# main_16_writer.net
KiCad netlist of a schematic drawn in EAGLE
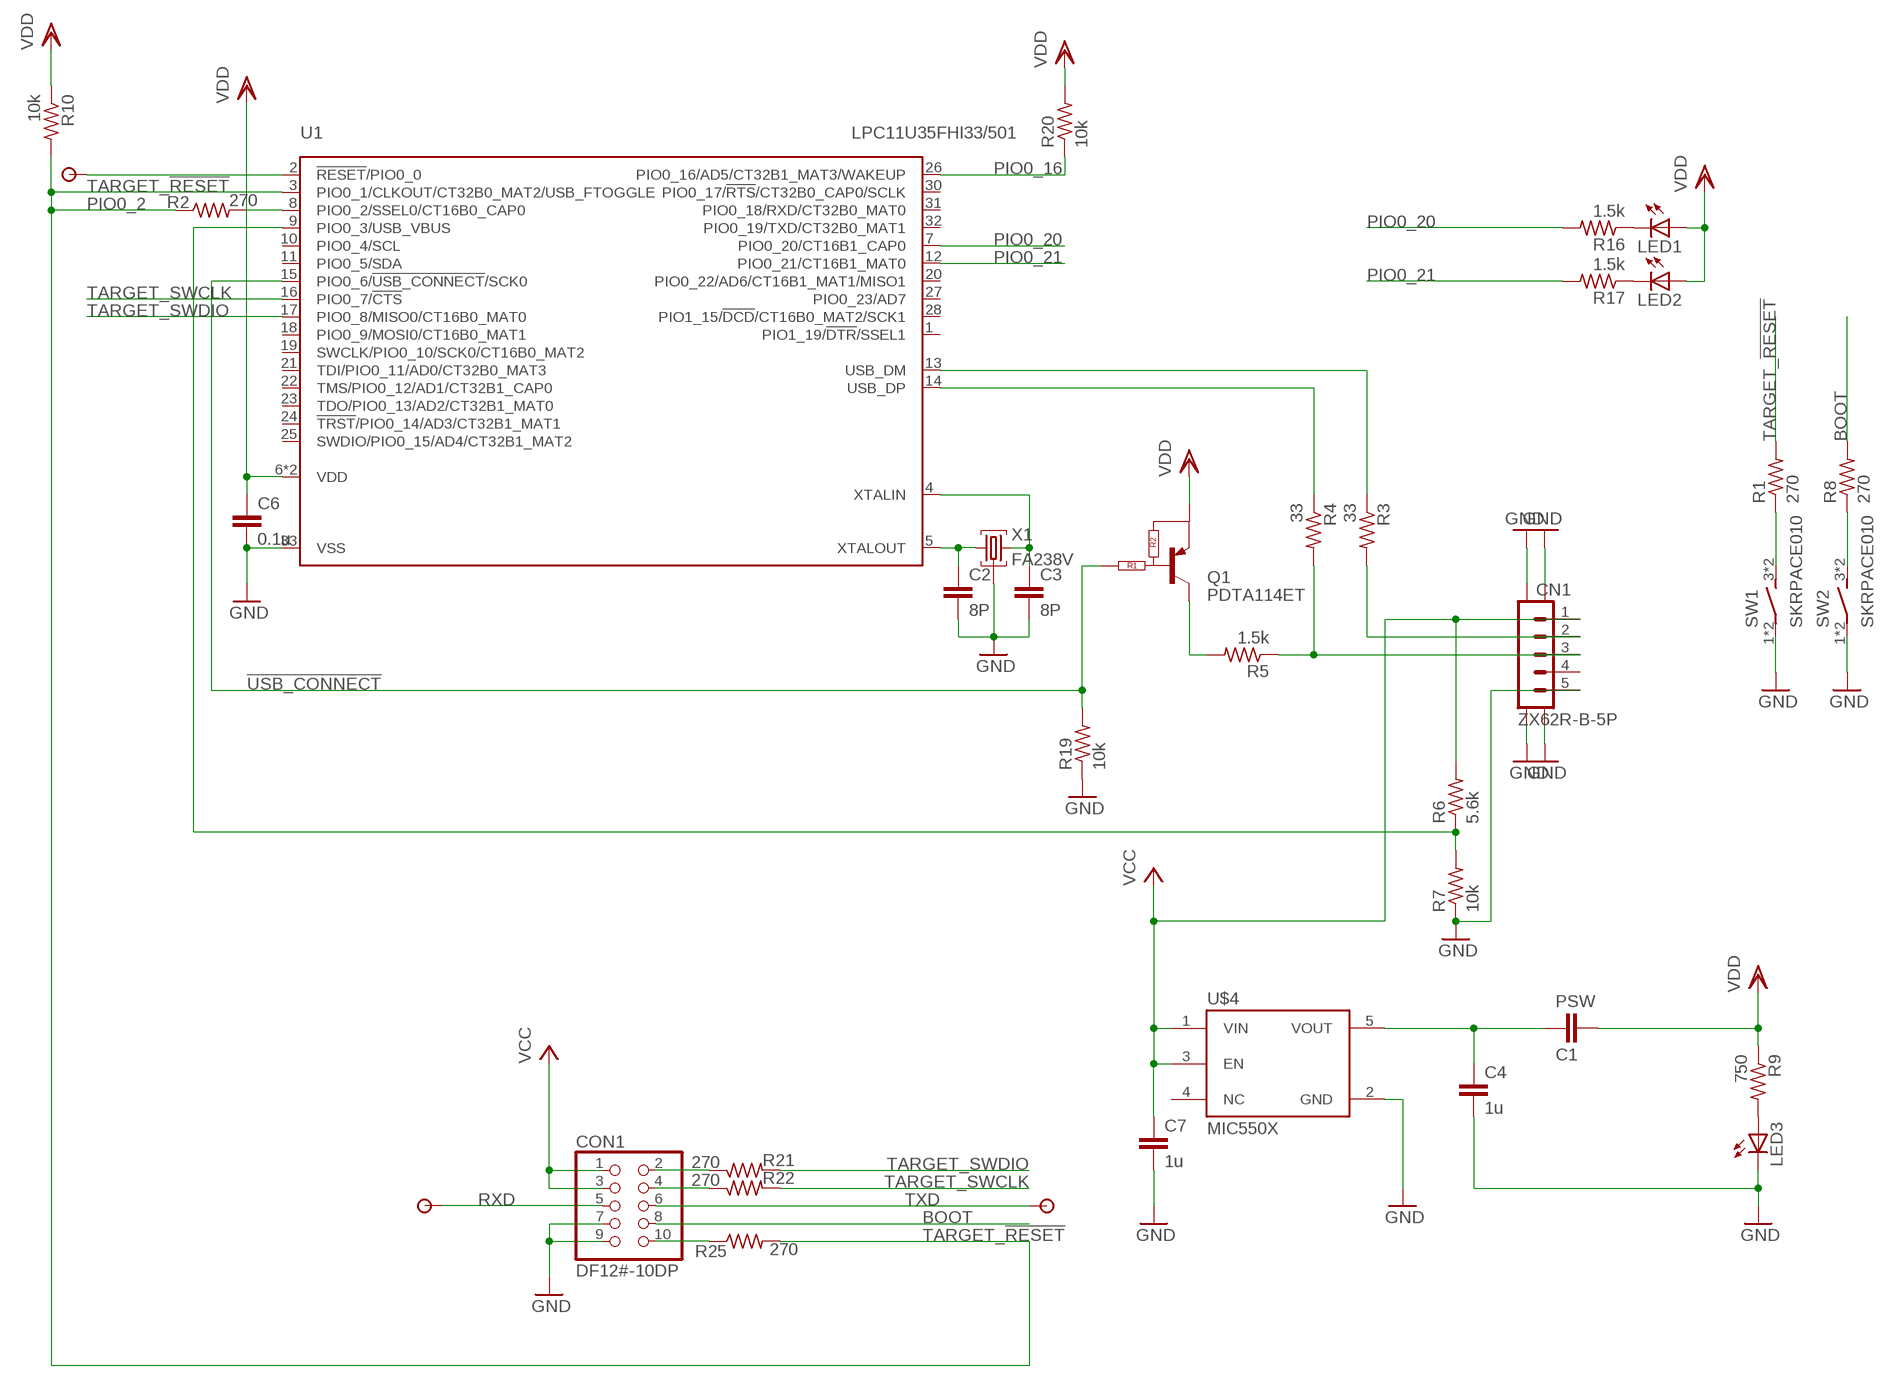
[diagram p0: schematic, sheet 1]

(export (version "E")
  (design (tool "Eeschema 10.0.6"))
  (components
    (comp (ref "C1")
      (value "PSW")
      (footprint "eagle-import:C3225")
      (libsource (lib "eagle-import") (part "C-EUC3225"))
    )
    (comp (ref "C2")
      (value "8P")
      (footprint "eagle-import:C0402")
      (libsource (lib "eagle-import") (part "C-EUC0402"))
    )
    (comp (ref "C3")
      (value "8P")
      (footprint "eagle-import:C0402")
      (libsource (lib "eagle-import") (part "C-EUC0402"))
    )
    (comp (ref "C4")
      (value "1u")
      (footprint "eagle-import:C0402")
      (libsource (lib "eagle-import") (part "C-EUC0402"))
    )
    (comp (ref "C6")
      (value "0.1u")
      (footprint "eagle-import:C0402")
      (libsource (lib "eagle-import") (part "C-EUC0402"))
    )
    (comp (ref "C7")
      (value "1u")
      (footprint "eagle-import:C0402")
      (libsource (lib "eagle-import") (part "C-EUC0402"))
    )
    (comp (ref "CN1")
      (value "ZX62R-B-5P")
      (footprint "eagle-import:MICRO-B")
      (libsource (lib "eagle-import") (part "ZX62R-B-5P"))
    )
    (comp (ref "CON1")
      (value "DF12#-10DP")
      (footprint "eagle-import:DF12D-10DP")
      (libsource (lib "eagle-import") (part "DF12#-10DP"))
    )
    (comp (ref "LED1")
      (value "LEDSML0603")
      (footprint "eagle-import:SML0603")
      (libsource (lib "eagle-import") (part "LEDSML0603"))
    )
    (comp (ref "LED2")
      (value "LEDSML0603")
      (footprint "eagle-import:SML0603")
      (libsource (lib "eagle-import") (part "LEDSML0603"))
    )
    (comp (ref "LED3")
      (value "LEDSML0603")
      (footprint "eagle-import:SML0603")
      (libsource (lib "eagle-import") (part "LEDSML0603"))
    )
    (comp (ref "Q1")
      (value "PDTA114ET")
      (footprint "eagle-import:SOT23")
      (libsource (lib "eagle-import") (part "PDTA114TE"))
    )
    (comp (ref "R1")
      (value "270")
      (footprint "eagle-import:R0402")
      (libsource (lib "eagle-import") (part "R-US_R0402"))
    )
    (comp (ref "R2")
      (value "270")
      (footprint "eagle-import:R0402")
      (libsource (lib "eagle-import") (part "R-US_R0402"))
    )
    (comp (ref "R3")
      (value "33")
      (footprint "eagle-import:R0402")
      (libsource (lib "eagle-import") (part "R-US_R0402"))
    )
    (comp (ref "R4")
      (value "33")
      (footprint "eagle-import:R0402")
      (libsource (lib "eagle-import") (part "R-US_R0402"))
    )
    (comp (ref "R5")
      (value "1.5k")
      (footprint "eagle-import:R0402")
      (libsource (lib "eagle-import") (part "R-US_R0402"))
    )
    (comp (ref "R6")
      (value "5.6k")
      (footprint "eagle-import:R0402")
      (libsource (lib "eagle-import") (part "R-US_R0402"))
    )
    (comp (ref "R7")
      (value "10k")
      (footprint "eagle-import:R0402")
      (libsource (lib "eagle-import") (part "R-US_R0402"))
    )
    (comp (ref "R8")
      (value "270")
      (footprint "eagle-import:R0402")
      (libsource (lib "eagle-import") (part "R-US_R0402"))
    )
    (comp (ref "R9")
      (value "750")
      (footprint "eagle-import:R0402")
      (libsource (lib "eagle-import") (part "R-US_R0402"))
    )
    (comp (ref "R10")
      (value "10k")
      (footprint "eagle-import:R0402")
      (libsource (lib "eagle-import") (part "R-US_R0402"))
    )
    (comp (ref "R16")
      (value "1.5k")
      (footprint "eagle-import:R0402")
      (libsource (lib "eagle-import") (part "R-US_R0402"))
    )
    (comp (ref "R17")
      (value "1.5k")
      (footprint "eagle-import:R0402")
      (libsource (lib "eagle-import") (part "R-US_R0402"))
    )
    (comp (ref "R19")
      (value "10k")
      (footprint "eagle-import:R0402")
      (libsource (lib "eagle-import") (part "R-US_R0402"))
    )
    (comp (ref "R20")
      (value "10k")
      (footprint "eagle-import:R0402")
      (libsource (lib "eagle-import") (part "R-US_R0402"))
    )
    (comp (ref "R21")
      (value "270")
      (footprint "eagle-import:R0402")
      (libsource (lib "eagle-import") (part "R-US_R0402"))
    )
    (comp (ref "R22")
      (value "270")
      (footprint "eagle-import:R0402")
      (libsource (lib "eagle-import") (part "R-US_R0402"))
    )
    (comp (ref "R25")
      (value "270")
      (footprint "eagle-import:R0402")
      (libsource (lib "eagle-import") (part "R-US_R0402"))
    )
    (comp (ref "SW1")
      (value "SKRPACE010")
      (footprint "eagle-import:SKRPACE010")
      (libsource (lib "eagle-import") (part "SKRPACE010"))
    )
    (comp (ref "SW2")
      (value "SKRPACE010")
      (footprint "eagle-import:SKRPACE010")
      (libsource (lib "eagle-import") (part "SKRPACE010"))
    )
    (comp (ref "U$1")
      (value "TESTPAD")
      (footprint "eagle-import:TESTPAD")
      (libsource (lib "eagle-import") (part "TESTPAD"))
    )
    (comp (ref "U$2")
      (value "TESTPAD")
      (footprint "eagle-import:TESTPAD")
      (libsource (lib "eagle-import") (part "TESTPAD"))
    )
    (comp (ref "U$3")
      (value "TESTPAD")
      (footprint "eagle-import:TESTPAD")
      (libsource (lib "eagle-import") (part "TESTPAD"))
    )
    (comp (ref "U$4")
      (value "MIC550X")
      (footprint "eagle-import:SOT23_5PIN")
      (libsource (lib "eagle-import") (part "MIC550X"))
    )
    (comp (ref "U1")
      (value "LPC11U35FHI33/501")
      (footprint "eagle-import:SOT617-3")
      (libsource (lib "eagle-import") (part "LPC11U35FHI33/501"))
    )
    (comp (ref "X1")
      (value "FA238V")
      (footprint "eagle-import:V66RA")
      (libsource (lib "eagle-import") (part "FA238V"))
    )
  )
  (nets
    (net (code "1") (name "/BOOT") (class "Default")
      (node (ref "CON1") (pin "8") (pinfunction "8_8") (pintype "passive"))
      (node (ref "R8") (pin "2") (pinfunction "2_2") (pintype "passive"))
    )
    (net (code "2") (name "/PIO0_2") (class "Default")
      (node (ref "R2") (pin "2") (pinfunction "2_2") (pintype "passive"))
      (node (ref "U1") (pin "8") (pinfunction "PIO0_2/SSEL0/CT16B0_CAP0_8") (pintype "bidirectional"))
    )
    (net (code "3") (name "/PIO0_16") (class "Default")
      (node (ref "R20") (pin "1") (pinfunction "1_1") (pintype "passive"))
      (node (ref "U1") (pin "26") (pinfunction "PIO0_16/AD5/CT32B1_MAT3/WAKEUP_26") (pintype "bidirectional"))
    )
    (net (code "4") (name "/PIO0_20") (class "Default")
      (node (ref "R16") (pin "2") (pinfunction "2_2") (pintype "passive"))
      (node (ref "U1") (pin "7") (pinfunction "PIO0_20/CT16B1_CAP0_7") (pintype "bidirectional"))
    )
    (net (code "5") (name "/PIO0_21") (class "Default")
      (node (ref "R17") (pin "2") (pinfunction "2_2") (pintype "passive"))
      (node (ref "U1") (pin "12") (pinfunction "PIO0_21/CT16B1_MAT0_12") (pintype "bidirectional"))
    )
    (net (code "6") (name "/RXD") (class "Default")
      (node (ref "CON1") (pin "5") (pinfunction "5_5") (pintype "passive"))
      (node (ref "U$2") (pin "P$1") (pinfunction "P$1_P$1") (pintype "passive"))
    )
    (net (code "7") (name "/TARGET_SWCLK") (class "Default")
      (node (ref "R22") (pin "2") (pinfunction "2_2") (pintype "passive"))
      (node (ref "U1") (pin "16") (pinfunction "PIO0_7/~{CTS}_16") (pintype "bidirectional"))
    )
    (net (code "8") (name "/TARGET_SWDIO") (class "Default")
      (node (ref "R21") (pin "2") (pinfunction "2_2") (pintype "passive"))
      (node (ref "U1") (pin "17") (pinfunction "PIO0_8/MISO0/CT16B0_MAT0_17") (pintype "bidirectional"))
    )
    (net (code "9") (name "/TARGET_~{RESET}") (class "Default")
      (node (ref "R1") (pin "2") (pinfunction "2_2") (pintype "passive"))
      (node (ref "R10") (pin "2") (pinfunction "2_2") (pintype "passive"))
      (node (ref "R2") (pin "1") (pinfunction "1_1") (pintype "passive"))
      (node (ref "R25") (pin "2") (pinfunction "2_2") (pintype "passive"))
      (node (ref "U1") (pin "3") (pinfunction "PIO0_1/CLKOUT/CT32B0_MAT2/USB_FTOGGLE_3") (pintype "bidirectional"))
    )
    (net (code "10") (name "/TXD") (class "Default")
      (node (ref "CON1") (pin "6") (pinfunction "6_6") (pintype "passive"))
      (node (ref "U$1") (pin "P$1") (pinfunction "P$1_P$1") (pintype "passive"))
    )
    (net (code "11") (name "/~{USB_CONNECT}") (class "Default")
      (node (ref "Q1") (pin "1") (pinfunction "INPUT_1") (pintype "passive"))
      (node (ref "R19") (pin "2") (pinfunction "2_2") (pintype "passive"))
      (node (ref "U1") (pin "15") (pinfunction "PIO0_6/~{USB_CONNECT}/SCK0_15") (pintype "bidirectional"))
    )
    (net (code "12") (name "GND") (class "Default")
      (node (ref "C2") (pin "2") (pinfunction "2_2") (pintype "passive"))
      (node (ref "C3") (pin "2") (pinfunction "2_2") (pintype "passive"))
      (node (ref "C4") (pin "2") (pinfunction "2_2") (pintype "passive"))
      (node (ref "C6") (pin "2") (pinfunction "2_2") (pintype "passive"))
      (node (ref "C7") (pin "2") (pinfunction "2_2") (pintype "passive"))
      (node (ref "CN1") (pin "5") (pinfunction "1.VBUS_5") (pintype "passive"))
      (node (ref "CN1") (pin "CASE@1") (pinfunction "1_CASE@1") (pintype "bidirectional"))
      (node (ref "CN1") (pin "CASE@2") (pinfunction "2_CASE@2") (pintype "bidirectional"))
      (node (ref "CN1") (pin "CASE@3") (pinfunction "3_CASE@3") (pintype "bidirectional"))
      (node (ref "CN1") (pin "CASE@4") (pinfunction "4_CASE@4") (pintype "bidirectional"))
      (node (ref "CON1") (pin "7") (pinfunction "7_7") (pintype "passive"))
      (node (ref "CON1") (pin "9") (pinfunction "9_9") (pintype "passive"))
      (node (ref "LED3") (pin "C") (pinfunction "C_C") (pintype "passive"))
      (node (ref "R19") (pin "1") (pinfunction "1_1") (pintype "passive"))
      (node (ref "R7") (pin "1") (pinfunction "1_1") (pintype "passive"))
      (node (ref "SW1") (pin "1") (pinfunction "P_1") (pintype "passive"))
      (node (ref "SW1") (pin "2") (pinfunction "P_2") (pintype "passive"))
      (node (ref "SW2") (pin "1") (pinfunction "P_1") (pintype "passive"))
      (node (ref "SW2") (pin "2") (pinfunction "P_2") (pintype "passive"))
      (node (ref "U$4") (pin "2") (pinfunction "GND_2") (pintype "power_in"))
      (node (ref "U1") (pin "33") (pinfunction "VSS_33") (pintype "power_in"))
      (node (ref "X1") (pin "P2GND") (pinfunction "GND_P2GND") (pintype "bidirectional"))
      (node (ref "X1") (pin "P4GND") (pinfunction "GND_P4GND") (pintype "bidirectional"))
    )
    (net (code "13") (name "Net-(CN1-3.D+)") (class "Default")
      (node (ref "CN1") (pin "3") (pinfunction "3.D+_3") (pintype "passive"))
      (node (ref "R4") (pin "2") (pinfunction "2_2") (pintype "passive"))
      (node (ref "R5") (pin "1") (pinfunction "1_1") (pintype "passive"))
    )
    (net (code "14") (name "Net-(CN1-4.ID)") (class "Default")
      (node (ref "CN1") (pin "2") (pinfunction "4.ID_2") (pintype "passive"))
      (node (ref "R3") (pin "2") (pinfunction "2_2") (pintype "passive"))
    )
    (net (code "15") (name "Net-(CON1-Pad2)") (class "Default")
      (node (ref "CON1") (pin "2") (pinfunction "2_2") (pintype "passive"))
      (node (ref "R21") (pin "1") (pinfunction "1_1") (pintype "passive"))
    )
    (net (code "16") (name "Net-(CON1-Pad4)") (class "Default")
      (node (ref "CON1") (pin "4") (pinfunction "4_4") (pintype "passive"))
      (node (ref "R22") (pin "1") (pinfunction "1_1") (pintype "passive"))
    )
    (net (code "17") (name "Net-(CON1-Pad10)") (class "Default")
      (node (ref "CON1") (pin "10") (pinfunction "10_10") (pintype "passive"))
      (node (ref "R25") (pin "1") (pinfunction "1_1") (pintype "passive"))
    )
    (net (code "18") (name "Net-(LED1-PadC)") (class "Default")
      (node (ref "LED1") (pin "C") (pinfunction "C_C") (pintype "passive"))
      (node (ref "R16") (pin "1") (pinfunction "1_1") (pintype "passive"))
    )
    (net (code "19") (name "Net-(LED2-PadC)") (class "Default")
      (node (ref "LED2") (pin "C") (pinfunction "C_C") (pintype "passive"))
      (node (ref "R17") (pin "1") (pinfunction "1_1") (pintype "passive"))
    )
    (net (code "20") (name "Net-(LED3-PadA)") (class "Default")
      (node (ref "LED3") (pin "A") (pinfunction "A_A") (pintype "passive"))
      (node (ref "R9") (pin "2") (pinfunction "2_2") (pintype "passive"))
    )
    (net (code "21") (name "Net-(Q1-C)") (class "Default")
      (node (ref "Q1") (pin "3") (pinfunction "C_3") (pintype "passive"))
      (node (ref "R5") (pin "2") (pinfunction "2_2") (pintype "passive"))
    )
    (net (code "22") (name "Net-(R1-Pad1)") (class "Default")
      (node (ref "R1") (pin "1") (pinfunction "1_1") (pintype "passive"))
      (node (ref "SW1") (pin "3") (pinfunction "S_3") (pintype "passive"))
      (node (ref "SW1") (pin "4") (pinfunction "S_4") (pintype "passive"))
    )
    (net (code "23") (name "Net-(R8-Pad1)") (class "Default")
      (node (ref "R8") (pin "1") (pinfunction "1_1") (pintype "passive"))
      (node (ref "SW2") (pin "3") (pinfunction "S_3") (pintype "passive"))
      (node (ref "SW2") (pin "4") (pinfunction "S_4") (pintype "passive"))
    )
    (net (code "24") (name "Net-(U$4-VOUT)") (class "Default")
      (node (ref "C1") (pin "2") (pinfunction "2_2") (pintype "passive"))
      (node (ref "C4") (pin "1") (pinfunction "1_1") (pintype "passive"))
      (node (ref "U$4") (pin "5") (pinfunction "VOUT_5") (pintype "output"))
    )
    (net (code "25") (name "Net-(U1-PIO0_3{slash}USB_VBUS)") (class "Default")
      (node (ref "R6") (pin "1") (pinfunction "1_1") (pintype "passive"))
      (node (ref "R7") (pin "2") (pinfunction "2_2") (pintype "passive"))
      (node (ref "U1") (pin "9") (pinfunction "PIO0_3/USB_VBUS_9") (pintype "bidirectional"))
    )
    (net (code "26") (name "Net-(U1-USB_DM)") (class "Default")
      (node (ref "R3") (pin "1") (pinfunction "1_1") (pintype "passive"))
      (node (ref "U1") (pin "13") (pinfunction "USB_DM_13") (pintype "bidirectional"))
    )
    (net (code "27") (name "Net-(U1-USB_DP)") (class "Default")
      (node (ref "R4") (pin "1") (pinfunction "1_1") (pintype "passive"))
      (node (ref "U1") (pin "14") (pinfunction "USB_DP_14") (pintype "bidirectional"))
    )
    (net (code "28") (name "Net-(U1-XTALIN)") (class "Default")
      (node (ref "C3") (pin "1") (pinfunction "1_1") (pintype "passive"))
      (node (ref "U1") (pin "4") (pinfunction "XTALIN_4") (pintype "input"))
      (node (ref "X1") (pin "P3X2") (pinfunction "X2_P3X2") (pintype "output"))
    )
    (net (code "29") (name "Net-(U1-XTALOUT)") (class "Default")
      (node (ref "C2") (pin "1") (pinfunction "1_1") (pintype "passive"))
      (node (ref "U1") (pin "5") (pinfunction "XTALOUT_5") (pintype "output"))
      (node (ref "X1") (pin "P1X1") (pinfunction "X1_P1X1") (pintype "output"))
    )
    (net (code "30") (name "Net-(U1-~{RESET}{slash}PIO0_0)") (class "Default")
      (node (ref "U$3") (pin "P$1") (pinfunction "P$1_P$1") (pintype "passive"))
      (node (ref "U1") (pin "2") (pinfunction "~{RESET}/PIO0_0_2") (pintype "bidirectional"))
    )
    (net (code "31") (name "VCC") (class "Default")
      (node (ref "C7") (pin "1") (pinfunction "1_1") (pintype "passive"))
      (node (ref "CN1") (pin "1") (pinfunction "5.GND_1") (pintype "passive"))
      (node (ref "CON1") (pin "1") (pinfunction "1_1") (pintype "passive"))
      (node (ref "CON1") (pin "3") (pinfunction "3_3") (pintype "passive"))
      (node (ref "R6") (pin "2") (pinfunction "2_2") (pintype "passive"))
      (node (ref "U$4") (pin "1") (pinfunction "VIN_1") (pintype "input"))
      (node (ref "U$4") (pin "3") (pinfunction "EN_3") (pintype "input"))
    )
    (net (code "32") (name "VDD") (class "Default")
      (node (ref "C1") (pin "1") (pinfunction "1_1") (pintype "passive"))
      (node (ref "C6") (pin "1") (pinfunction "1_1") (pintype "passive"))
      (node (ref "LED1") (pin "A") (pinfunction "A_A") (pintype "passive"))
      (node (ref "LED2") (pin "A") (pinfunction "A_A") (pintype "passive"))
      (node (ref "Q1") (pin "2") (pinfunction "E_2") (pintype "passive"))
      (node (ref "R10") (pin "1") (pinfunction "1_1") (pintype "passive"))
      (node (ref "R20") (pin "2") (pinfunction "2_2") (pintype "passive"))
      (node (ref "R9") (pin "1") (pinfunction "1_1") (pintype "passive"))
      (node (ref "U1") (pin "29") (pinfunction "VDD_29") (pintype "power_in"))
      (node (ref "U1") (pin "6") (pinfunction "VDD_6") (pintype "power_in"))
    )
    (net (code "33") (name "unconnected-(CN1-2.D--Pad4)") (class "Default")
      (node (ref "CN1") (pin "4") (pinfunction "2.D-_4") (pintype "passive"))
    )
    (net (code "34") (name "unconnected-(U$4-NC-Pad4)") (class "Default")
      (node (ref "U$4") (pin "4") (pinfunction "NC_4") (pintype "no_connect"))
    )
    (net (code "35") (name "unconnected-(U1-PIO0_4{slash}SCL-Pad10)") (class "Default")
      (node (ref "U1") (pin "10") (pinfunction "PIO0_4/SCL_10") (pintype "bidirectional"))
    )
    (net (code "36") (name "unconnected-(U1-PIO0_5{slash}SDA-Pad11)") (class "Default")
      (node (ref "U1") (pin "11") (pinfunction "PIO0_5/SDA_11") (pintype "bidirectional"))
    )
    (net (code "37") (name "unconnected-(U1-PIO0_9{slash}MOSI0{slash}CT16B0_MAT1-Pad18)") (class "Default")
      (node (ref "U1") (pin "18") (pinfunction "PIO0_9/MOSI0/CT16B0_MAT1_18") (pintype "bidirectional"))
    )
    (net (code "38") (name "unconnected-(U1-PIO0_17{slash}~{RTS}{slash}CT32B0_CAP0{slash}SCLK-Pad30)") (class "Default")
      (node (ref "U1") (pin "30") (pinfunction "PIO0_17/~{RTS}/CT32B0_CAP0/SCLK_30") (pintype "bidirectional"))
    )
    (net (code "39") (name "unconnected-(U1-PIO0_18{slash}RXD{slash}CT32B0_MAT0-Pad31)") (class "Default")
      (node (ref "U1") (pin "31") (pinfunction "PIO0_18/RXD/CT32B0_MAT0_31") (pintype "bidirectional"))
    )
    (net (code "40") (name "unconnected-(U1-PIO0_19{slash}TXD{slash}CT32B0_MAT1-Pad32)") (class "Default")
      (node (ref "U1") (pin "32") (pinfunction "PIO0_19/TXD/CT32B0_MAT1_32") (pintype "bidirectional"))
    )
    (net (code "41") (name "unconnected-(U1-PIO0_22{slash}AD6{slash}CT16B1_MAT1{slash}MISO1-Pad20)") (class "Default")
      (node (ref "U1") (pin "20") (pinfunction "PIO0_22/AD6/CT16B1_MAT1/MISO1_20") (pintype "bidirectional"))
    )
    (net (code "42") (name "unconnected-(U1-PIO0_23{slash}AD7-Pad27)") (class "Default")
      (node (ref "U1") (pin "27") (pinfunction "PIO0_23/AD7_27") (pintype "bidirectional"))
    )
    (net (code "43") (name "unconnected-(U1-PIO1_15{slash}~{DCD}{slash}CT16B0_MAT2{slash}SCK1-Pad28)") (class "Default")
      (node (ref "U1") (pin "28") (pinfunction "PIO1_15/~{DCD}/CT16B0_MAT2/SCK1_28") (pintype "bidirectional"))
    )
    (net (code "44") (name "unconnected-(U1-PIO1_19{slash}~{DTR}{slash}SSEL1-Pad1)") (class "Default")
      (node (ref "U1") (pin "1") (pinfunction "PIO1_19/~{DTR}/SSEL1_1") (pintype "bidirectional"))
    )
    (net (code "45") (name "unconnected-(U1-SWCLK{slash}PIO0_10{slash}SCK0{slash}CT16B0_MAT2-Pad19)") (class "Default")
      (node (ref "U1") (pin "19") (pinfunction "SWCLK/PIO0_10/SCK0/CT16B0_MAT2_19") (pintype "bidirectional"))
    )
    (net (code "46") (name "unconnected-(U1-SWDIO{slash}PIO0_15{slash}AD4{slash}CT32B1_MAT2-Pad25)") (class "Default")
      (node (ref "U1") (pin "25") (pinfunction "SWDIO/PIO0_15/AD4/CT32B1_MAT2_25") (pintype "bidirectional"))
    )
    (net (code "47") (name "unconnected-(U1-TDI{slash}PIO0_11{slash}AD0{slash}CT32B0_MAT3-Pad21)") (class "Default")
      (node (ref "U1") (pin "21") (pinfunction "TDI/PIO0_11/AD0/CT32B0_MAT3_21") (pintype "bidirectional"))
    )
    (net (code "48") (name "unconnected-(U1-TDO{slash}PIO0_13{slash}AD2{slash}CT32B1_MAT0-Pad23)") (class "Default")
      (node (ref "U1") (pin "23") (pinfunction "TDO/PIO0_13/AD2/CT32B1_MAT0_23") (pintype "bidirectional"))
    )
    (net (code "49") (name "unconnected-(U1-TMS{slash}PIO0_12{slash}AD1{slash}CT32B1_CAP0-Pad22)") (class "Default")
      (node (ref "U1") (pin "22") (pinfunction "TMS/PIO0_12/AD1/CT32B1_CAP0_22") (pintype "bidirectional"))
    )
    (net (code "50") (name "unconnected-(U1-~{TRST}{slash}PIO0_14{slash}AD3{slash}CT32B1_MAT1-Pad24)") (class "Default")
      (node (ref "U1") (pin "24") (pinfunction "~{TRST}/PIO0_14/AD3/CT32B1_MAT1_24") (pintype "bidirectional"))
    )
  )
)
